# Sheet1.net
KiCad netlist of a schematic drawn in Altium Designer
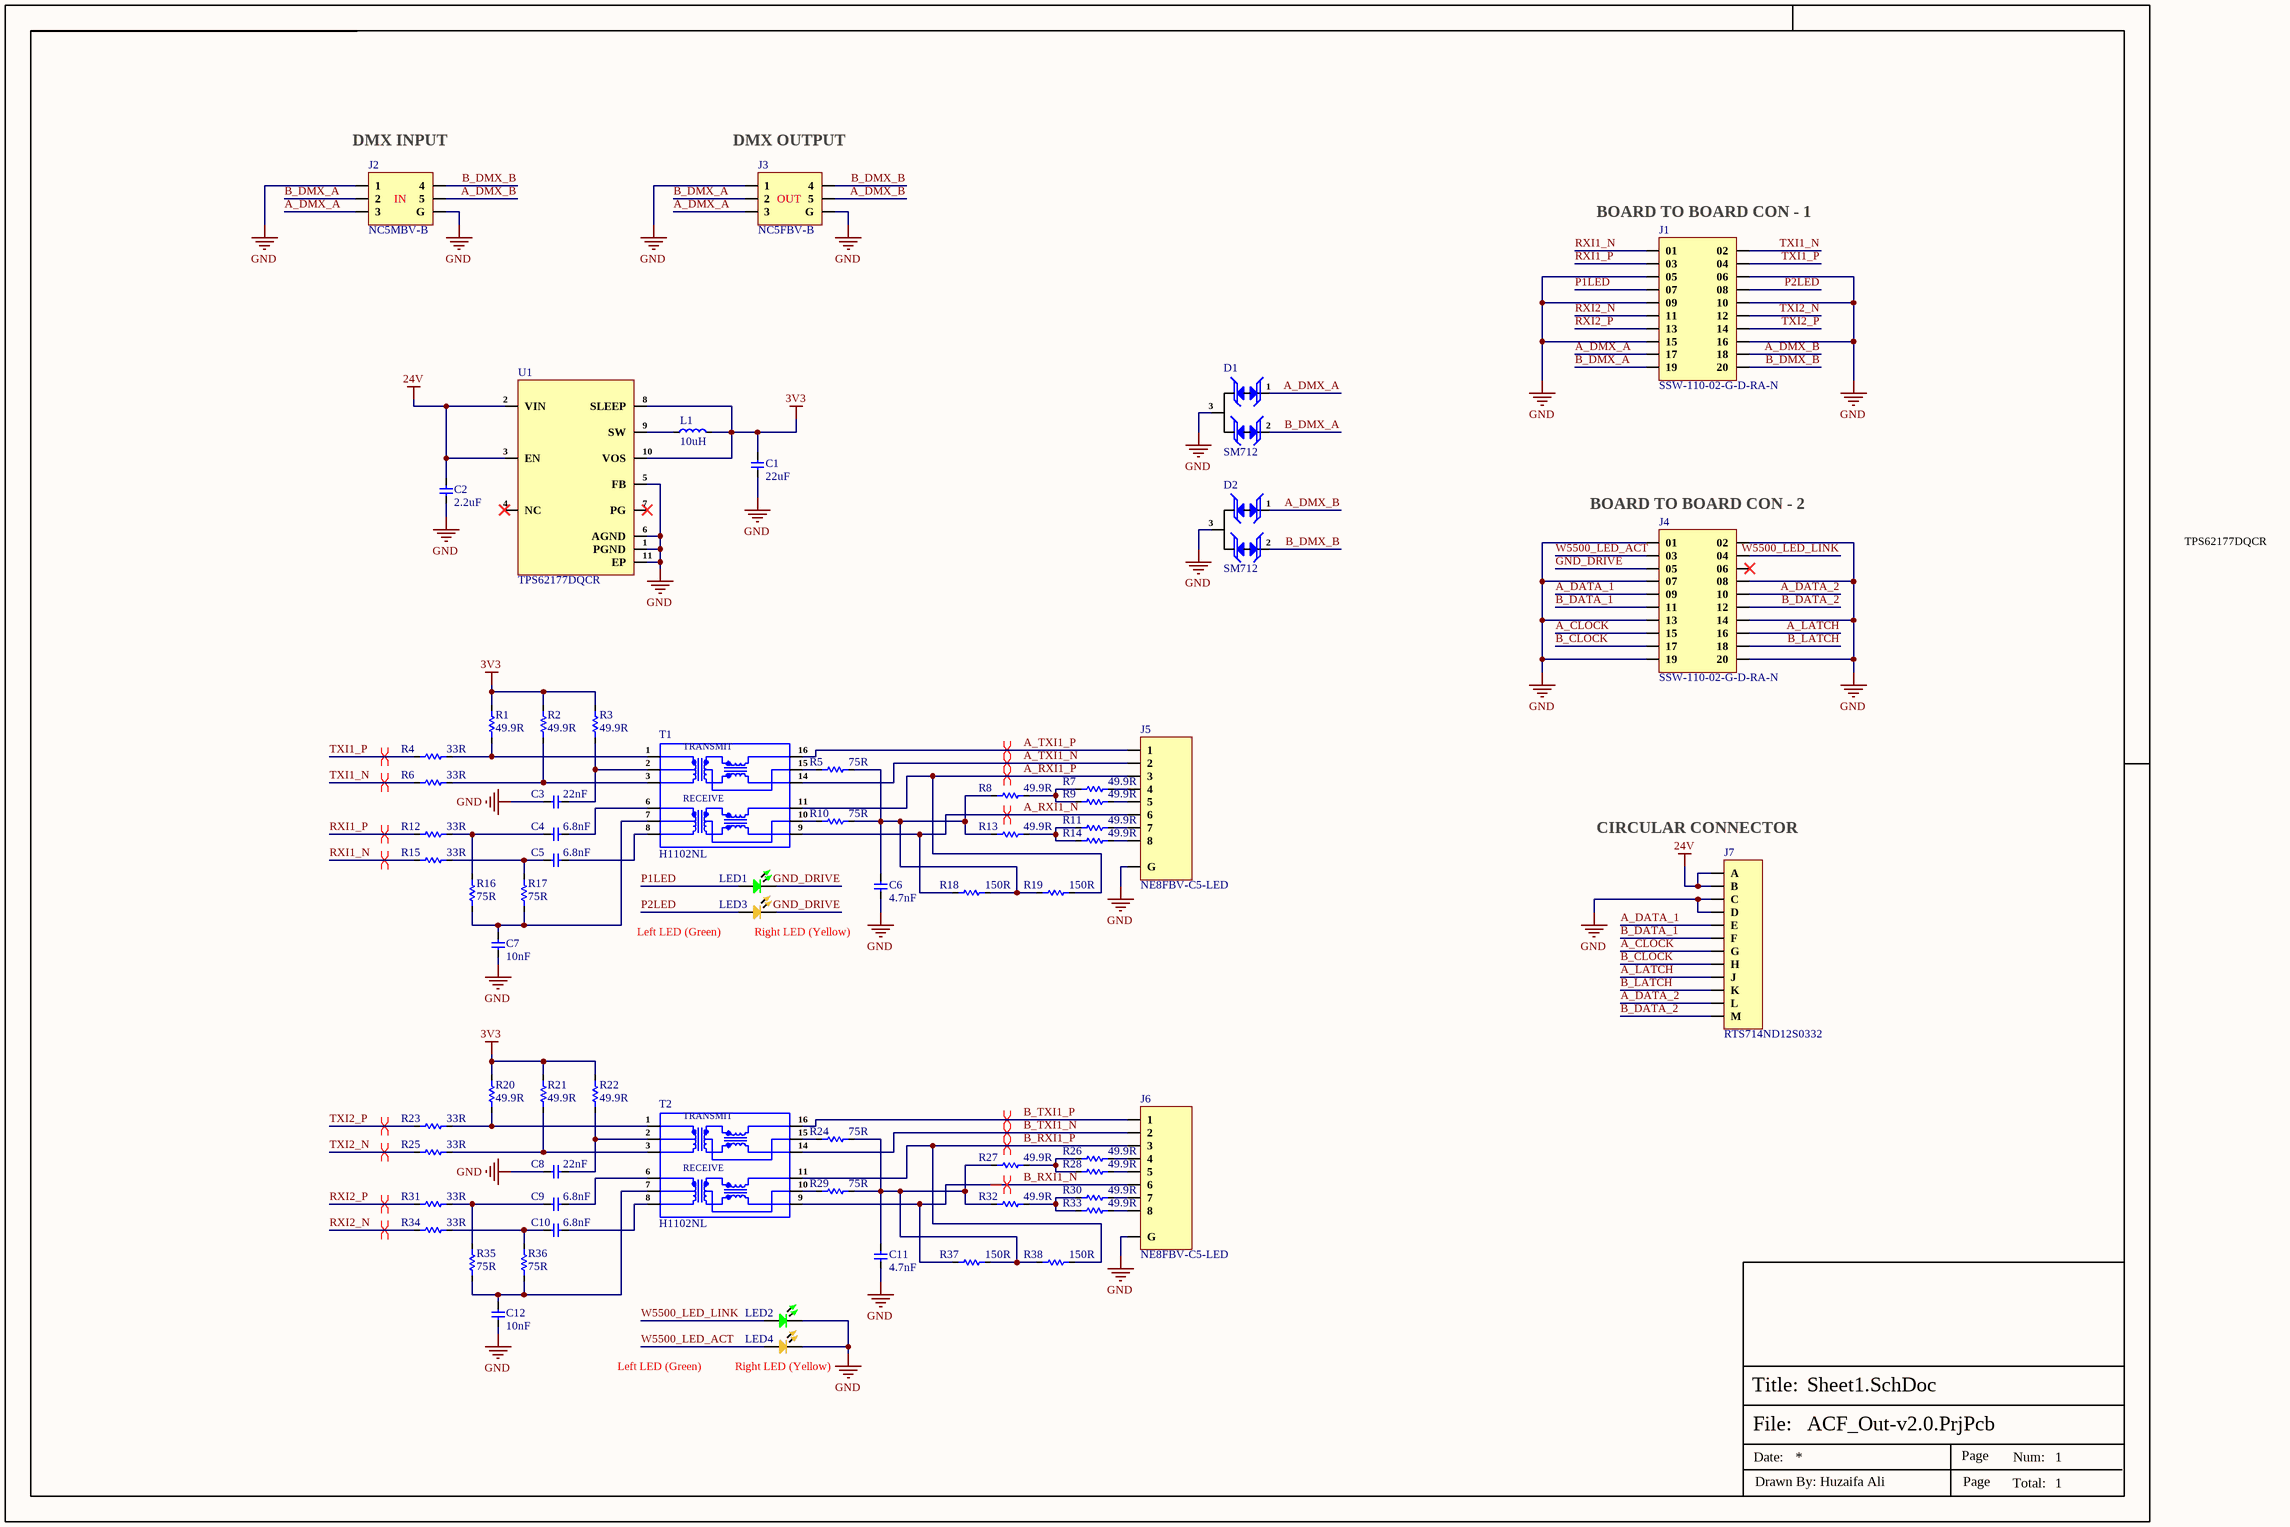
[diagram p0: Sheet1.SchDoc]

(export (version "E")
  (design (tool "Eeschema 10.0.6"))
  (components
    (comp (ref "C1")
      (value "22uF")
      (footprint "Cap-0805")
      (description "CAP CER 22UF 25V X5R 0805")
      (fields
        (field (name "MANUFACTURER") "Yageo")
        (field (name "MANUFACTURER PART NUMBER") "CC0805MKX5R8BB226")
      )
      (libsource (lib "eSpark Libraries") (part "CC0805MKX5R8BB226"))
    )
    (comp (ref "C2")
      (value "2.2uF")
      (footprint "Cap-0805")
      (description "CAP CER 2.2UF 50V X7R 0805")
      (fields (field (name "LCSC PART NUMBER") "C125847") (field (name "MANUFACTURER") "Yageo"))
      (libsource (lib "eSpark Libraries") (part "CC0805KKX7R9BB225"))
    )
    (comp (ref "C3")
      (value "22nF")
      (footprint "Cap-0603")
      (description "CAP CER 0.022UF 50V X7R 0603")
      (fields
        (field (name "MANUFACTURER") "Yageo")
        (field (name "MANUFACTURER PART NUMBER") "CC0603KRX7R9BB223")
      )
      (libsource (lib "eSpark Libraries") (part "CC0603KRX7R9BB223"))
    )
    (comp (ref "C4")
      (value "6.8nF")
      (footprint "Cap-0603")
      (description "50V 6.8nF X7R ±10% 0603")
      (fields (field (name "MANUFACTURER") "FH") (field (name "MANUFACTURER PART NUMBER") "0603B682K500NT"))
      (libsource (lib "eSpark Libraries") (part "0603B682K500NT"))
    )
    (comp (ref "C5")
      (value "6.8nF")
      (footprint "Cap-0603")
      (description "50V 6.8nF X7R ±10% 0603")
      (fields (field (name "MANUFACTURER") "FH") (field (name "MANUFACTURER PART NUMBER") "0603B682K500NT"))
      (libsource (lib "eSpark Libraries") (part "0603B682K500NT"))
    )
    (comp (ref "C6")
      (value "4.7nF")
      (footprint "Cap-1206")
      (description "CAP CER 4700PF 1KV X7R 1206")
      (fields
        (field (name "MANUFACTURER") "Yageo")
        (field (name "MANUFACTURER PART NUMBER") "CC1206KKX7RCBB472")
      )
      (libsource (lib "eSpark Libraries") (part "CC1206KKX7RCBB472"))
    )
    (comp (ref "C7")
      (value "10nF")
      (footprint "Cap-0603")
      (description "CAP CER 10000PF 100V X7R 0603")
      (fields (field (name "LCSC PART NUMBER") "C107059") (field (name "MANUFACTURER") "Yageo"))
      (libsource (lib "eSpark Libraries") (part "CC0603KRX7R0BB103"))
    )
    (comp (ref "C8")
      (value "22nF")
      (footprint "Cap-0603")
      (description "CAP CER 0.022UF 50V X7R 0603")
      (fields
        (field (name "MANUFACTURER") "Yageo")
        (field (name "MANUFACTURER PART NUMBER") "CC0603KRX7R9BB223")
      )
      (libsource (lib "eSpark Libraries") (part "CC0603KRX7R9BB223"))
    )
    (comp (ref "C9")
      (value "6.8nF")
      (footprint "Cap-0603")
      (description "50V 6.8nF X7R ±10% 0603")
      (fields (field (name "MANUFACTURER") "FH") (field (name "MANUFACTURER PART NUMBER") "0603B682K500NT"))
      (libsource (lib "eSpark Libraries") (part "0603B682K500NT"))
    )
    (comp (ref "C10")
      (value "6.8nF")
      (footprint "Cap-0603")
      (description "50V 6.8nF X7R ±10% 0603")
      (fields (field (name "MANUFACTURER") "FH") (field (name "MANUFACTURER PART NUMBER") "0603B682K500NT"))
      (libsource (lib "eSpark Libraries") (part "0603B682K500NT"))
    )
    (comp (ref "C11")
      (value "4.7nF")
      (footprint "Cap-1206")
      (description "CAP CER 4700PF 1KV X7R 1206")
      (fields
        (field (name "MANUFACTURER") "Yageo")
        (field (name "MANUFACTURER PART NUMBER") "CC1206KKX7RCBB472")
      )
      (libsource (lib "eSpark Libraries") (part "CC1206KKX7RCBB472"))
    )
    (comp (ref "C12")
      (value "10nF")
      (footprint "Cap-0603")
      (description "CAP CER 10000PF 100V X7R 0603")
      (fields (field (name "LCSC PART NUMBER") "C107059") (field (name "MANUFACTURER") "Yageo"))
      (libsource (lib "eSpark Libraries") (part "CC0603KRX7R0BB103"))
    )
    (comp (ref "D1")
      (value "SM712")
      (footprint "SOT-23")
      (description "SOT-23 TVS ROHS")
      (fields (field (name "MANUFACTURER") "TECH PUBLIC") (field (name "LCSC PART NUMBER") "C521963"))
      (libsource (lib "eSpark Libraries") (part "SM712"))
    )
    (comp (ref "D2")
      (value "SM712")
      (footprint "SOT-23")
      (description "SOT-23 TVS ROHS")
      (fields (field (name "MANUFACTURER") "TECH PUBLIC") (field (name "LCSC PART NUMBER") "C521963"))
      (libsource (lib "eSpark Libraries") (part "SM712"))
    )
    (comp (ref "J1")
      (value "SSW-110-02-G-D-RA-N")
      (footprint "SSW-110-02-G-D-RA-N")
      (description "CONN RCPT 20POS 0.1 GOLD PCB R/A")
      (fields (field (name "MANUFACTURER") "Samtec"))
      (libsource (lib "eSpark Libraries") (part "SSW-110-02-G-D-RA-N"))
    )
    (comp (ref "J2")
      (value "NC5MBV-B")
      (footprint "NC5MBV-B")
      (description "XLR Connectors 5P M RECEPT B SER PCBV PN 1 GRD SEP BK")
      (fields (field (name "MANUFACTURER") "Neutrik"))
      (libsource (lib "eSpark Libraries") (part "NC5MBV-B"))
    )
    (comp (ref "J3")
      (value "NC5FBV-B")
      (footprint "NC5FBV-B")
      (description "XLR Connectors 5P M RECEPT B SER PCBV PN 1 GRD SEP BK")
      (fields (field (name "MANUFACTURER") "Neutrik"))
      (libsource (lib "eSpark Libraries") (part "NC5FBV-B"))
    )
    (comp (ref "J4")
      (value "SSW-110-02-G-D-RA-N")
      (footprint "SSW-110-02-G-D-RA-N")
      (description "CONN RCPT 20POS 0.1 GOLD PCB R/A")
      (fields (field (name "MANUFACTURER") "Samtec"))
      (libsource (lib "eSpark Libraries") (part "SSW-110-02-G-D-RA-N"))
    )
    (comp (ref "J5")
      (value "NE8FBV-C5-LED")
      (footprint "NE8FBV-C5-LED")
      (description "Modular Connectors / Ethernet Connectors RECP CAT5e B series PCBV, 24mm FP to PCB")
      (fields (field (name "MANUFACTURER") "Neutrik"))
      (libsource (lib "eSpark Libraries") (part "NE8FBV-C5-LED"))
    )
    (comp (ref "J6")
      (value "NE8FBV-C5-LED")
      (footprint "NE8FBV-C5-LED")
      (description "Modular Connectors / Ethernet Connectors RECP CAT5e B series PCBV, 24mm FP to PCB")
      (fields (field (name "MANUFACTURER") "Neutrik"))
      (libsource (lib "eSpark Libraries") (part "NE8FBV-C5-LED"))
    )
    (comp (ref "J7")
      (value "RTS714ND12S0332")
      (footprint "RTS714ND12S0332")
      (description "CONN RCPT FMALE 12P GOLD SOLDER")
      (fields (field (name "MANUFACTURER") "Amphenol Sine Systems"))
      (libsource (lib "eSpark Libraries") (part "RTS714ND12S0332"))
    )
    (comp (ref "L1")
      (value "10uH")
      (footprint "IND-1008 (2520 Metric)")
      (description "FIXED IND 10UH 1A 540 MOHM SMD")
      (fields
        (field (name "MANUFACTURER") "TDK")
        (field (name "MANUFACTURER PART NUMBER") "VLS252012HBX-100M-1")
      )
      (libsource (lib "eSpark Libraries") (part "VLS252012HBX-100M-1"))
    )
    (comp (ref "LED1")
      (value "Emerald")
      (footprint "TH LED 3mm_")
      (description "515nm~525nm -30℃~+85℃ Emerald 30° 200mW Plugin,D=3mm Light Emitting Diodes (LED) ROHS")
      (fields
        (field (name "MANUFACTURER") "Foshan NationStar Optoelectronics")
        (field (name "MANUFACTURER PART NUMBER") "NFD3401UGD")
      )
      (libsource (lib "eSpark Libraries") (part "NFD3401UGD"))
    )
    (comp (ref "LED2")
      (value "Emerald")
      (footprint "TH LED 3mm_")
      (description "515nm~525nm -30℃~+85℃ Emerald 30° 200mW Plugin,D=3mm Light Emitting Diodes (LED) ROHS")
      (fields
        (field (name "MANUFACTURER") "Foshan NationStar Optoelectronics")
        (field (name "MANUFACTURER PART NUMBER") "NFD3401UGD")
      )
      (libsource (lib "eSpark Libraries") (part "NFD3401UGD"))
    )
    (comp (ref "LED3")
      (value "Yellow")
      (footprint "TH LED Yellow 3MM")
      (description "585nm~595nm -30℃~+85℃ Yellow 30° 200mW Plugin,D=3mm Light Emitting Diodes (LED) ROHS")
      (fields
        (field (name "MANUFACTURER") "Foshan NationStar Optoelectronics")
        (field (name "MANUFACTURER PART NUMBER") "NFD3401UYD")
      )
      (libsource (lib "eSpark Libraries") (part "NFD3401UYD"))
    )
    (comp (ref "LED4")
      (value "Yellow")
      (footprint "TH LED Yellow 3MM")
      (description "585nm~595nm -30℃~+85℃ Yellow 30° 200mW Plugin,D=3mm Light Emitting Diodes (LED) ROHS")
      (fields
        (field (name "MANUFACTURER") "Foshan NationStar Optoelectronics")
        (field (name "MANUFACTURER PART NUMBER") "NFD3401UYD")
      )
      (libsource (lib "eSpark Libraries") (part "NFD3401UYD"))
    )
    (comp (ref "R1")
      (value "49.9R")
      (footprint "Res-0603")
      (description "RES 49.9 OHM 1% 1/10W 0603")
      (fields
        (field (name "MANUFACTURER") "Yageo")
        (field (name "MANUFACTURER PART NUMBER") "RC0603FR-0749R9L")
      )
      (libsource (lib "eSpark Libraries") (part "RC0603FR-0749R9L"))
    )
    (comp (ref "R2")
      (value "49.9R")
      (footprint "Res-0603")
      (description "RES 49.9 OHM 1% 1/10W 0603")
      (fields
        (field (name "MANUFACTURER") "Yageo")
        (field (name "MANUFACTURER PART NUMBER") "RC0603FR-0749R9L")
      )
      (libsource (lib "eSpark Libraries") (part "RC0603FR-0749R9L"))
    )
    (comp (ref "R3")
      (value "49.9R")
      (footprint "Res-0603")
      (description "RES 49.9 OHM 1% 1/10W 0603")
      (fields
        (field (name "MANUFACTURER") "Yageo")
        (field (name "MANUFACTURER PART NUMBER") "RC0603FR-0749R9L")
      )
      (libsource (lib "eSpark Libraries") (part "RC0603FR-0749R9L"))
    )
    (comp (ref "R4")
      (value "33R")
      (footprint "Res-0603")
      (description "RES SMD 0603 33 Ohm 1% 1/10W")
      (fields
        (field (name "MANUFACTURER") "Yageo")
        (field (name "MANUFACTURER PART NUMBER") "RC0603FR-0733RL")
      )
      (libsource (lib "eSpark Libraries") (part "RC0603FR-0733RL"))
    )
    (comp (ref "R5")
      (value "75R")
      (footprint "Res-0603")
      (description "RES 75 OHM 1% 1/10W 0603")
      (fields
        (field (name "MANUFACTURER") "Yageo")
        (field (name "MANUFACTURER PART NUMBER") "RC0603FR-0775RL")
      )
      (libsource (lib "eSpark Libraries") (part "RC0603FR-0775RL"))
    )
    (comp (ref "R6")
      (value "33R")
      (footprint "Res-0603")
      (description "RES SMD 0603 33 Ohm 1% 1/10W")
      (fields
        (field (name "MANUFACTURER") "Yageo")
        (field (name "MANUFACTURER PART NUMBER") "RC0603FR-0733RL")
      )
      (libsource (lib "eSpark Libraries") (part "RC0603FR-0733RL"))
    )
    (comp (ref "R7")
      (value "49.9R")
      (footprint "Res-0603")
      (description "RES 49.9 OHM 1% 1/10W 0603")
      (fields
        (field (name "MANUFACTURER") "Yageo")
        (field (name "MANUFACTURER PART NUMBER") "RC0603FR-0749R9L")
      )
      (libsource (lib "eSpark Libraries") (part "RC0603FR-0749R9L"))
    )
    (comp (ref "R8")
      (value "49.9R")
      (footprint "Res-0603")
      (description "RES 49.9 OHM 1% 1/10W 0603")
      (fields
        (field (name "MANUFACTURER") "Yageo")
        (field (name "MANUFACTURER PART NUMBER") "RC0603FR-0749R9L")
      )
      (libsource (lib "eSpark Libraries") (part "RC0603FR-0749R9L"))
    )
    (comp (ref "R9")
      (value "49.9R")
      (footprint "Res-0603")
      (description "RES 49.9 OHM 1% 1/10W 0603")
      (fields
        (field (name "MANUFACTURER") "Yageo")
        (field (name "MANUFACTURER PART NUMBER") "RC0603FR-0749R9L")
      )
      (libsource (lib "eSpark Libraries") (part "RC0603FR-0749R9L"))
    )
    (comp (ref "R10")
      (value "75R")
      (footprint "Res-0603")
      (description "RES 75 OHM 1% 1/10W 0603")
      (fields
        (field (name "MANUFACTURER") "Yageo")
        (field (name "MANUFACTURER PART NUMBER") "RC0603FR-0775RL")
      )
      (libsource (lib "eSpark Libraries") (part "RC0603FR-0775RL"))
    )
    (comp (ref "R11")
      (value "49.9R")
      (footprint "Res-0603")
      (description "RES 49.9 OHM 1% 1/10W 0603")
      (fields
        (field (name "MANUFACTURER") "Yageo")
        (field (name "MANUFACTURER PART NUMBER") "RC0603FR-0749R9L")
      )
      (libsource (lib "eSpark Libraries") (part "RC0603FR-0749R9L"))
    )
    (comp (ref "R12")
      (value "33R")
      (footprint "Res-0603")
      (description "RES SMD 0603 33 Ohm 1% 1/10W")
      (fields
        (field (name "MANUFACTURER") "Yageo")
        (field (name "MANUFACTURER PART NUMBER") "RC0603FR-0733RL")
      )
      (libsource (lib "eSpark Libraries") (part "RC0603FR-0733RL"))
    )
    (comp (ref "R13")
      (value "49.9R")
      (footprint "Res-0603")
      (description "RES 49.9 OHM 1% 1/10W 0603")
      (fields
        (field (name "MANUFACTURER") "Yageo")
        (field (name "MANUFACTURER PART NUMBER") "RC0603FR-0749R9L")
      )
      (libsource (lib "eSpark Libraries") (part "RC0603FR-0749R9L"))
    )
    (comp (ref "R14")
      (value "49.9R")
      (footprint "Res-0603")
      (description "RES 49.9 OHM 1% 1/10W 0603")
      (fields
        (field (name "MANUFACTURER") "Yageo")
        (field (name "MANUFACTURER PART NUMBER") "RC0603FR-0749R9L")
      )
      (libsource (lib "eSpark Libraries") (part "RC0603FR-0749R9L"))
    )
    (comp (ref "R15")
      (value "33R")
      (footprint "Res-0603")
      (description "RES SMD 0603 33 Ohm 1% 1/10W")
      (fields
        (field (name "MANUFACTURER") "Yageo")
        (field (name "MANUFACTURER PART NUMBER") "RC0603FR-0733RL")
      )
      (libsource (lib "eSpark Libraries") (part "RC0603FR-0733RL"))
    )
    (comp (ref "R16")
      (value "75R")
      (footprint "Res-0603")
      (description "RES 75 OHM 1% 1/10W 0603")
      (fields
        (field (name "MANUFACTURER") "Yageo")
        (field (name "MANUFACTURER PART NUMBER") "RC0603FR-0775RL")
      )
      (libsource (lib "eSpark Libraries") (part "RC0603FR-0775RL"))
    )
    (comp (ref "R17")
      (value "75R")
      (footprint "Res-0603")
      (description "RES 75 OHM 1% 1/10W 0603")
      (fields
        (field (name "MANUFACTURER") "Yageo")
        (field (name "MANUFACTURER PART NUMBER") "RC0603FR-0775RL")
      )
      (libsource (lib "eSpark Libraries") (part "RC0603FR-0775RL"))
    )
    (comp (ref "R18")
      (value "150R")
      (footprint "Res-0603")
      (description "RES SMD 150OHM 1/10W 0603")
      (fields
        (field (name "MANUFACTURER") "Yageo")
        (field (name "MANUFACTURER PART NUMBER") "RC0603FR-07150RL")
      )
      (libsource (lib "eSpark Libraries") (part "RC0603FR-07150RL"))
    )
    (comp (ref "R19")
      (value "150R")
      (footprint "Res-0603")
      (description "RES SMD 150OHM 1/10W 0603")
      (fields
        (field (name "MANUFACTURER") "Yageo")
        (field (name "MANUFACTURER PART NUMBER") "RC0603FR-07150RL")
      )
      (libsource (lib "eSpark Libraries") (part "RC0603FR-07150RL"))
    )
    (comp (ref "R20")
      (value "49.9R")
      (footprint "Res-0603")
      (description "RES 49.9 OHM 1% 1/10W 0603")
      (fields
        (field (name "MANUFACTURER") "Yageo")
        (field (name "MANUFACTURER PART NUMBER") "RC0603FR-0749R9L")
      )
      (libsource (lib "eSpark Libraries") (part "RC0603FR-0749R9L"))
    )
    (comp (ref "R21")
      (value "49.9R")
      (footprint "Res-0603")
      (description "RES 49.9 OHM 1% 1/10W 0603")
      (fields
        (field (name "MANUFACTURER") "Yageo")
        (field (name "MANUFACTURER PART NUMBER") "RC0603FR-0749R9L")
      )
      (libsource (lib "eSpark Libraries") (part "RC0603FR-0749R9L"))
    )
    (comp (ref "R22")
      (value "49.9R")
      (footprint "Res-0603")
      (description "RES 49.9 OHM 1% 1/10W 0603")
      (fields
        (field (name "MANUFACTURER") "Yageo")
        (field (name "MANUFACTURER PART NUMBER") "RC0603FR-0749R9L")
      )
      (libsource (lib "eSpark Libraries") (part "RC0603FR-0749R9L"))
    )
    (comp (ref "R23")
      (value "33R")
      (footprint "Res-0603")
      (description "RES SMD 0603 33 Ohm 1% 1/10W")
      (fields
        (field (name "MANUFACTURER") "Yageo")
        (field (name "MANUFACTURER PART NUMBER") "RC0603FR-0733RL")
      )
      (libsource (lib "eSpark Libraries") (part "RC0603FR-0733RL"))
    )
    (comp (ref "R24")
      (value "75R")
      (footprint "Res-0603")
      (description "RES 75 OHM 1% 1/10W 0603")
      (fields
        (field (name "MANUFACTURER") "Yageo")
        (field (name "MANUFACTURER PART NUMBER") "RC0603FR-0775RL")
      )
      (libsource (lib "eSpark Libraries") (part "RC0603FR-0775RL"))
    )
    (comp (ref "R25")
      (value "33R")
      (footprint "Res-0603")
      (description "RES SMD 0603 33 Ohm 1% 1/10W")
      (fields
        (field (name "MANUFACTURER") "Yageo")
        (field (name "MANUFACTURER PART NUMBER") "RC0603FR-0733RL")
      )
      (libsource (lib "eSpark Libraries") (part "RC0603FR-0733RL"))
    )
    (comp (ref "R26")
      (value "49.9R")
      (footprint "Res-0603")
      (description "RES 49.9 OHM 1% 1/10W 0603")
      (fields
        (field (name "MANUFACTURER") "Yageo")
        (field (name "MANUFACTURER PART NUMBER") "RC0603FR-0749R9L")
      )
      (libsource (lib "eSpark Libraries") (part "RC0603FR-0749R9L"))
    )
    (comp (ref "R27")
      (value "49.9R")
      (footprint "Res-0603")
      (description "RES 49.9 OHM 1% 1/10W 0603")
      (fields
        (field (name "MANUFACTURER") "Yageo")
        (field (name "MANUFACTURER PART NUMBER") "RC0603FR-0749R9L")
      )
      (libsource (lib "eSpark Libraries") (part "RC0603FR-0749R9L"))
    )
    (comp (ref "R28")
      (value "49.9R")
      (footprint "Res-0603")
      (description "RES 49.9 OHM 1% 1/10W 0603")
      (fields
        (field (name "MANUFACTURER") "Yageo")
        (field (name "MANUFACTURER PART NUMBER") "RC0603FR-0749R9L")
      )
      (libsource (lib "eSpark Libraries") (part "RC0603FR-0749R9L"))
    )
    (comp (ref "R29")
      (value "75R")
      (footprint "Res-0603")
      (description "RES 75 OHM 1% 1/10W 0603")
      (fields
        (field (name "MANUFACTURER") "Yageo")
        (field (name "MANUFACTURER PART NUMBER") "RC0603FR-0775RL")
      )
      (libsource (lib "eSpark Libraries") (part "RC0603FR-0775RL"))
    )
    (comp (ref "R30")
      (value "49.9R")
      (footprint "Res-0603")
      (description "RES 49.9 OHM 1% 1/10W 0603")
      (fields
        (field (name "MANUFACTURER") "Yageo")
        (field (name "MANUFACTURER PART NUMBER") "RC0603FR-0749R9L")
      )
      (libsource (lib "eSpark Libraries") (part "RC0603FR-0749R9L"))
    )
    (comp (ref "R31")
      (value "33R")
      (footprint "Res-0603")
      (description "RES SMD 0603 33 Ohm 1% 1/10W")
      (fields
        (field (name "MANUFACTURER") "Yageo")
        (field (name "MANUFACTURER PART NUMBER") "RC0603FR-0733RL")
      )
      (libsource (lib "eSpark Libraries") (part "RC0603FR-0733RL"))
    )
    (comp (ref "R32")
      (value "49.9R")
      (footprint "Res-0603")
      (description "RES 49.9 OHM 1% 1/10W 0603")
      (fields
        (field (name "MANUFACTURER") "Yageo")
        (field (name "MANUFACTURER PART NUMBER") "RC0603FR-0749R9L")
      )
      (libsource (lib "eSpark Libraries") (part "RC0603FR-0749R9L"))
    )
    (comp (ref "R33")
      (value "49.9R")
      (footprint "Res-0603")
      (description "RES 49.9 OHM 1% 1/10W 0603")
      (fields
        (field (name "MANUFACTURER") "Yageo")
        (field (name "MANUFACTURER PART NUMBER") "RC0603FR-0749R9L")
      )
      (libsource (lib "eSpark Libraries") (part "RC0603FR-0749R9L"))
    )
    (comp (ref "R34")
      (value "33R")
      (footprint "Res-0603")
      (description "RES SMD 0603 33 Ohm 1% 1/10W")
      (fields
        (field (name "MANUFACTURER") "Yageo")
        (field (name "MANUFACTURER PART NUMBER") "RC0603FR-0733RL")
      )
      (libsource (lib "eSpark Libraries") (part "RC0603FR-0733RL"))
    )
    (comp (ref "R35")
      (value "75R")
      (footprint "Res-0603")
      (description "RES 75 OHM 1% 1/10W 0603")
      (fields
        (field (name "MANUFACTURER") "Yageo")
        (field (name "MANUFACTURER PART NUMBER") "RC0603FR-0775RL")
      )
      (libsource (lib "eSpark Libraries") (part "RC0603FR-0775RL"))
    )
    (comp (ref "R36")
      (value "75R")
      (footprint "Res-0603")
      (description "RES 75 OHM 1% 1/10W 0603")
      (fields
        (field (name "MANUFACTURER") "Yageo")
        (field (name "MANUFACTURER PART NUMBER") "RC0603FR-0775RL")
      )
      (libsource (lib "eSpark Libraries") (part "RC0603FR-0775RL"))
    )
    (comp (ref "R37")
      (value "150R")
      (footprint "Res-0603")
      (description "RES SMD 150OHM 1/10W 0603")
      (fields
        (field (name "MANUFACTURER") "Yageo")
        (field (name "MANUFACTURER PART NUMBER") "RC0603FR-07150RL")
      )
      (libsource (lib "eSpark Libraries") (part "RC0603FR-07150RL"))
    )
    (comp (ref "R38")
      (value "150R")
      (footprint "Res-0603")
      (description "RES SMD 150OHM 1/10W 0603")
      (fields
        (field (name "MANUFACTURER") "Yageo")
        (field (name "MANUFACTURER PART NUMBER") "RC0603FR-07150RL")
      )
      (libsource (lib "eSpark Libraries") (part "RC0603FR-07150RL"))
    )
    (comp (ref "T1")
      (value "H1102NL")
      (footprint "H1102NLT")
      (description "XFRMR MAGNETIC 1PORT 1:1 10/100")
      (fields (field (name "MANUFACTURER") "Pulse") (field (name "LCSC PART NUMBER") "C18584"))
      (libsource (lib "eSpark Libraries") (part "H1102NL"))
    )
    (comp (ref "T2")
      (value "H1102NL")
      (footprint "H1102NLT")
      (description "XFRMR MAGNETIC 1PORT 1:1 10/100")
      (fields (field (name "MANUFACTURER") "Pulse") (field (name "LCSC PART NUMBER") "C18584"))
      (libsource (lib "eSpark Libraries") (part "H1102NL"))
    )
    (comp (ref "U1")
      (value "TPS62177DQCR")
      (footprint "10-WSON (3x2)")
      (description "IC REG BUCK 3.3V 500MA 10WSON")
      (fields (field (name "LCSC PART NUMBER") "C91241") (field (name "MANUFACTURER") "Texas Instruments"))
      (libsource (lib "eSpark Libraries") (part "TPS62177DQCR"))
    )
  )
  (nets
    (net (code "1") (name "/A_CLOCK") (class "Default")
      (node (ref "J4") (pin "15") (pinfunction "15_15") (pintype "passive"))
      (node (ref "J7") (pin "G") (pinfunction "G_G") (pintype "passive"))
    )
    (net (code "2") (name "/A_DATA_1") (class "Default")
      (node (ref "J4") (pin "09") (pinfunction "09_09") (pintype "passive"))
      (node (ref "J7") (pin "E") (pinfunction "E_E") (pintype "passive"))
    )
    (net (code "3") (name "/A_DATA_2") (class "Default")
      (node (ref "J4") (pin "10") (pinfunction "10_10") (pintype "passive"))
      (node (ref "J7") (pin "L") (pinfunction "L_L") (pintype "passive"))
    )
    (net (code "4") (name "/A_DMX_A") (class "Default")
      (node (ref "D1") (pin "1") (pinfunction "I/O1_1") (pintype "passive"))
      (node (ref "J1") (pin "17") (pinfunction "17_17") (pintype "passive"))
      (node (ref "J2") (pin "3") (pinfunction "3_3") (pintype "passive"))
      (node (ref "J3") (pin "3") (pinfunction "3_3") (pintype "passive"))
    )
    (net (code "5") (name "/A_DMX_B") (class "Default")
      (node (ref "D2") (pin "1") (pinfunction "I/O1_1") (pintype "passive"))
      (node (ref "J1") (pin "18") (pinfunction "18_18") (pintype "passive"))
      (node (ref "J2") (pin "5") (pinfunction "5_5") (pintype "passive"))
      (node (ref "J3") (pin "5") (pinfunction "5_5") (pintype "passive"))
    )
    (net (code "6") (name "/A_LATCH") (class "Default")
      (node (ref "J4") (pin "16") (pinfunction "16_16") (pintype "passive"))
      (node (ref "J7") (pin "J") (pinfunction "J_J") (pintype "passive"))
    )
    (net (code "7") (name "/A_RXI1_N") (class "Default")
      (node (ref "J5") (pin "6") (pinfunction "6_6") (pintype "passive"))
      (node (ref "R18") (pin "2") (pinfunction "2_2") (pintype "passive"))
      (node (ref "T1") (pin "9") (pinfunction "9_9") (pintype "passive"))
    )
    (net (code "8") (name "/A_RXI1_P") (class "Default")
      (node (ref "J5") (pin "3") (pinfunction "3_3") (pintype "passive"))
      (node (ref "R19") (pin "1") (pinfunction "1_1") (pintype "passive"))
      (node (ref "T1") (pin "11") (pinfunction "11_11") (pintype "passive"))
    )
    (net (code "9") (name "/A_TXI1_N") (class "Default")
      (node (ref "J5") (pin "2") (pinfunction "2_2") (pintype "passive"))
      (node (ref "T1") (pin "14") (pinfunction "14_14") (pintype "passive"))
    )
    (net (code "10") (name "/A_TXI1_P") (class "Default")
      (node (ref "J5") (pin "1") (pinfunction "1_1") (pintype "passive"))
      (node (ref "T1") (pin "16") (pinfunction "16_16") (pintype "passive"))
    )
    (net (code "11") (name "/B_CLOCK") (class "Default")
      (node (ref "J4") (pin "17") (pinfunction "17_17") (pintype "passive"))
      (node (ref "J7") (pin "H") (pinfunction "H_H") (pintype "passive"))
    )
    (net (code "12") (name "/B_DATA_1") (class "Default")
      (node (ref "J4") (pin "11") (pinfunction "11_11") (pintype "passive"))
      (node (ref "J7") (pin "F") (pinfunction "F_F") (pintype "passive"))
    )
    (net (code "13") (name "/B_DATA_2") (class "Default")
      (node (ref "J4") (pin "12") (pinfunction "12_12") (pintype "passive"))
      (node (ref "J7") (pin "M") (pinfunction "M_M") (pintype "passive"))
    )
    (net (code "14") (name "/B_DMX_A") (class "Default")
      (node (ref "D1") (pin "2") (pinfunction "I/O2_2") (pintype "passive"))
      (node (ref "J1") (pin "19") (pinfunction "19_19") (pintype "passive"))
      (node (ref "J2") (pin "2") (pinfunction "2_2") (pintype "passive"))
      (node (ref "J3") (pin "2") (pinfunction "2_2") (pintype "passive"))
    )
    (net (code "15") (name "/B_DMX_B") (class "Default")
      (node (ref "D2") (pin "2") (pinfunction "I/O2_2") (pintype "passive"))
      (node (ref "J1") (pin "20") (pinfunction "20_20") (pintype "passive"))
      (node (ref "J2") (pin "4") (pinfunction "4_4") (pintype "passive"))
      (node (ref "J3") (pin "4") (pinfunction "4_4") (pintype "passive"))
    )
    (net (code "16") (name "/B_LATCH") (class "Default")
      (node (ref "J4") (pin "18") (pinfunction "18_18") (pintype "passive"))
      (node (ref "J7") (pin "K") (pinfunction "K_K") (pintype "passive"))
    )
    (net (code "17") (name "/B_RXI1_N") (class "Default")
      (node (ref "J6") (pin "6") (pinfunction "6_6") (pintype "passive"))
      (node (ref "R37") (pin "2") (pinfunction "2_2") (pintype "passive"))
      (node (ref "T2") (pin "9") (pinfunction "9_9") (pintype "passive"))
    )
    (net (code "18") (name "/B_RXI1_P") (class "Default")
      (node (ref "J6") (pin "3") (pinfunction "3_3") (pintype "passive"))
      (node (ref "R38") (pin "1") (pinfunction "1_1") (pintype "passive"))
      (node (ref "T2") (pin "11") (pinfunction "11_11") (pintype "passive"))
    )
    (net (code "19") (name "/B_TXI1_N") (class "Default")
      (node (ref "J6") (pin "2") (pinfunction "2_2") (pintype "passive"))
      (node (ref "T2") (pin "14") (pinfunction "14_14") (pintype "passive"))
    )
    (net (code "20") (name "/B_TXI1_P") (class "Default")
      (node (ref "J6") (pin "1") (pinfunction "1_1") (pintype "passive"))
      (node (ref "T2") (pin "16") (pinfunction "16_16") (pintype "passive"))
    )
    (net (code "21") (name "/GND_DRIVE") (class "Default")
      (node (ref "J4") (pin "05") (pinfunction "05_05") (pintype "passive"))
      (node (ref "LED1") (pin "1") (pinfunction "-_1") (pintype "passive"))
      (node (ref "LED3") (pin "2") (pinfunction "2_2") (pintype "passive"))
    )
    (net (code "22") (name "/P1LED") (class "Default")
      (node (ref "J1") (pin "07") (pinfunction "07_07") (pintype "passive"))
      (node (ref "LED1") (pin "2") (pinfunction "+_2") (pintype "passive"))
    )
    (net (code "23") (name "/P2LED") (class "Default")
      (node (ref "J1") (pin "08") (pinfunction "08_08") (pintype "passive"))
      (node (ref "LED3") (pin "1") (pinfunction "1_1") (pintype "passive"))
    )
    (net (code "24") (name "/RXI1_N") (class "Default")
      (node (ref "J1") (pin "01") (pinfunction "01_01") (pintype "passive"))
      (node (ref "R15") (pin "1") (pinfunction "1_1") (pintype "passive"))
    )
    (net (code "25") (name "/RXI1_P") (class "Default")
      (node (ref "J1") (pin "03") (pinfunction "03_03") (pintype "passive"))
      (node (ref "R12") (pin "1") (pinfunction "1_1") (pintype "passive"))
    )
    (net (code "26") (name "/RXI2_N") (class "Default")
      (node (ref "J1") (pin "11") (pinfunction "11_11") (pintype "passive"))
      (node (ref "R34") (pin "1") (pinfunction "1_1") (pintype "passive"))
    )
    (net (code "27") (name "/RXI2_P") (class "Default")
      (node (ref "J1") (pin "13") (pinfunction "13_13") (pintype "passive"))
      (node (ref "R31") (pin "1") (pinfunction "1_1") (pintype "passive"))
    )
    (net (code "28") (name "/TXI1_N") (class "Default")
      (node (ref "J1") (pin "02") (pinfunction "02_02") (pintype "passive"))
      (node (ref "R6") (pin "1") (pinfunction "1_1") (pintype "passive"))
    )
    (net (code "29") (name "/TXI1_P") (class "Default")
      (node (ref "J1") (pin "04") (pinfunction "04_04") (pintype "passive"))
      (node (ref "R4") (pin "1") (pinfunction "1_1") (pintype "passive"))
    )
    (net (code "30") (name "/TXI2_N") (class "Default")
      (node (ref "J1") (pin "12") (pinfunction "12_12") (pintype "passive"))
      (node (ref "R25") (pin "1") (pinfunction "1_1") (pintype "passive"))
    )
    (net (code "31") (name "/TXI2_P") (class "Default")
      (node (ref "J1") (pin "14") (pinfunction "14_14") (pintype "passive"))
      (node (ref "R23") (pin "1") (pinfunction "1_1") (pintype "passive"))
    )
    (net (code "32") (name "/W5500_LED_ACT") (class "Default")
      (node (ref "J4") (pin "03") (pinfunction "03_03") (pintype "passive"))
      (node (ref "LED4") (pin "1") (pinfunction "1_1") (pintype "passive"))
    )
    (net (code "33") (name "/W5500_LED_LINK") (class "Default")
      (node (ref "J4") (pin "04") (pinfunction "04_04") (pintype "passive"))
      (node (ref "LED2") (pin "2") (pinfunction "+_2") (pintype "passive"))
    )
    (net (code "34") (name "3V3") (class "Default")
      (node (ref "C1") (pin "2") (pinfunction "2_2") (pintype "passive"))
      (node (ref "L1") (pin "2") (pinfunction "2_2") (pintype "passive"))
      (node (ref "R1") (pin "1") (pinfunction "1_1") (pintype "passive"))
      (node (ref "R2") (pin "1") (pinfunction "1_1") (pintype "passive"))
      (node (ref "R20") (pin "1") (pinfunction "1_1") (pintype "passive"))
      (node (ref "R21") (pin "1") (pinfunction "1_1") (pintype "passive"))
      (node (ref "R22") (pin "1") (pinfunction "1_1") (pintype "passive"))
      (node (ref "R3") (pin "1") (pinfunction "1_1") (pintype "passive"))
      (node (ref "U1") (pin "10") (pinfunction "VOS_10") (pintype "passive"))
      (node (ref "U1") (pin "8") (pinfunction "SLEEP_8") (pintype "passive"))
    )
    (net (code "35") (name "24V") (class "Default")
      (node (ref "C2") (pin "2") (pinfunction "2_2") (pintype "passive"))
      (node (ref "J7") (pin "A") (pinfunction "A_A") (pintype "passive"))
      (node (ref "J7") (pin "B") (pinfunction "B_B") (pintype "passive"))
      (node (ref "U1") (pin "2") (pinfunction "VIN_2") (pintype "passive"))
      (node (ref "U1") (pin "3") (pinfunction "EN_3") (pintype "passive"))
    )
    (net (code "36") (name "GND") (class "Default")
      (node (ref "C1") (pin "1") (pinfunction "1_1") (pintype "passive"))
      (node (ref "C11") (pin "1") (pinfunction "1_1") (pintype "passive"))
      (node (ref "C12") (pin "1") (pinfunction "1_1") (pintype "passive"))
      (node (ref "C2") (pin "1") (pinfunction "1_1") (pintype "passive"))
      (node (ref "C3") (pin "1") (pinfunction "1_1") (pintype "passive"))
      (node (ref "C6") (pin "1") (pinfunction "1_1") (pintype "passive"))
      (node (ref "C7") (pin "1") (pinfunction "1_1") (pintype "passive"))
      (node (ref "C8") (pin "1") (pinfunction "1_1") (pintype "passive"))
      (node (ref "D1") (pin "3") (pinfunction "GND_3") (pintype "passive"))
      (node (ref "D2") (pin "3") (pinfunction "GND_3") (pintype "passive"))
      (node (ref "J1") (pin "05") (pinfunction "05_05") (pintype "passive"))
      (node (ref "J1") (pin "06") (pinfunction "06_06") (pintype "passive"))
      (node (ref "J1") (pin "09") (pinfunction "09_09") (pintype "passive"))
      (node (ref "J1") (pin "10") (pinfunction "10_10") (pintype "passive"))
      (node (ref "J1") (pin "15") (pinfunction "15_15") (pintype "passive"))
      (node (ref "J1") (pin "16") (pinfunction "16_16") (pintype "passive"))
      (node (ref "J2") (pin "1") (pinfunction "1_1") (pintype "passive"))
      (node (ref "J2") (pin "G") (pinfunction "G_G") (pintype "passive"))
      (node (ref "J3") (pin "1") (pinfunction "1_1") (pintype "passive"))
      (node (ref "J3") (pin "G") (pinfunction "G_G") (pintype "passive"))
      (node (ref "J4") (pin "01") (pinfunction "01_01") (pintype "passive"))
      (node (ref "J4") (pin "02") (pinfunction "02_02") (pintype "passive"))
      (node (ref "J4") (pin "07") (pinfunction "07_07") (pintype "passive"))
      (node (ref "J4") (pin "08") (pinfunction "08_08") (pintype "passive"))
      (node (ref "J4") (pin "13") (pinfunction "13_13") (pintype "passive"))
      (node (ref "J4") (pin "14") (pinfunction "14_14") (pintype "passive"))
      (node (ref "J4") (pin "19") (pinfunction "19_19") (pintype "passive"))
      (node (ref "J4") (pin "20") (pinfunction "20_20") (pintype "passive"))
      (node (ref "J5") (pin "G") (pinfunction "G_G") (pintype "power_in"))
      (node (ref "J6") (pin "G") (pinfunction "G_G") (pintype "power_in"))
      (node (ref "J7") (pin "C") (pinfunction "C_C") (pintype "passive"))
      (node (ref "J7") (pin "D") (pinfunction "D_D") (pintype "passive"))
      (node (ref "LED2") (pin "1") (pinfunction "-_1") (pintype "passive"))
      (node (ref "LED4") (pin "2") (pinfunction "2_2") (pintype "passive"))
      (node (ref "U1") (pin "1") (pinfunction "PGND_1") (pintype "passive"))
      (node (ref "U1") (pin "11") (pinfunction "EP_11") (pintype "passive"))
      (node (ref "U1") (pin "5") (pinfunction "FB_5") (pintype "passive"))
      (node (ref "U1") (pin "6") (pinfunction "AGND_6") (pintype "passive"))
    )
    (net (code "37") (name "Net-(C3-Pad2)") (class "Default")
      (node (ref "C3") (pin "2") (pinfunction "2_2") (pintype "passive"))
      (node (ref "R3") (pin "2") (pinfunction "2_2") (pintype "passive"))
      (node (ref "T1") (pin "2") (pinfunction "2_2") (pintype "passive"))
    )
    (net (code "38") (name "Net-(C4-Pad1)") (class "Default")
      (node (ref "C4") (pin "1") (pinfunction "1_1") (pintype "passive"))
      (node (ref "R12") (pin "2") (pinfunction "2_2") (pintype "passive"))
      (node (ref "R16") (pin "1") (pinfunction "1_1") (pintype "passive"))
    )
    (net (code "39") (name "Net-(C4-Pad2)") (class "Default")
      (node (ref "C4") (pin "2") (pinfunction "2_2") (pintype "passive"))
      (node (ref "T1") (pin "6") (pinfunction "6_6") (pintype "passive"))
    )
    (net (code "40") (name "Net-(C5-Pad1)") (class "Default")
      (node (ref "C5") (pin "1") (pinfunction "1_1") (pintype "passive"))
      (node (ref "R15") (pin "2") (pinfunction "2_2") (pintype "passive"))
      (node (ref "R17") (pin "1") (pinfunction "1_1") (pintype "passive"))
    )
    (net (code "41") (name "Net-(C5-Pad2)") (class "Default")
      (node (ref "C5") (pin "2") (pinfunction "2_2") (pintype "passive"))
      (node (ref "T1") (pin "8") (pinfunction "8_8") (pintype "passive"))
    )
    (net (code "42") (name "Net-(C6-Pad2)") (class "Default")
      (node (ref "C6") (pin "2") (pinfunction "2_2") (pintype "passive"))
      (node (ref "R10") (pin "1") (pinfunction "1_1") (pintype "passive"))
      (node (ref "R13") (pin "2") (pinfunction "2_2") (pintype "passive"))
      (node (ref "R18") (pin "1") (pinfunction "1_1") (pintype "passive"))
      (node (ref "R19") (pin "2") (pinfunction "2_2") (pintype "passive"))
      (node (ref "R5") (pin "1") (pinfunction "1_1") (pintype "passive"))
      (node (ref "R8") (pin "2") (pinfunction "2_2") (pintype "passive"))
    )
    (net (code "43") (name "Net-(C7-Pad2)") (class "Default")
      (node (ref "C7") (pin "2") (pinfunction "2_2") (pintype "passive"))
      (node (ref "R16") (pin "2") (pinfunction "2_2") (pintype "passive"))
      (node (ref "R17") (pin "2") (pinfunction "2_2") (pintype "passive"))
      (node (ref "T1") (pin "7") (pinfunction "7_7") (pintype "passive"))
    )
    (net (code "44") (name "Net-(C8-Pad2)") (class "Default")
      (node (ref "C8") (pin "2") (pinfunction "2_2") (pintype "passive"))
      (node (ref "R22") (pin "2") (pinfunction "2_2") (pintype "passive"))
      (node (ref "T2") (pin "2") (pinfunction "2_2") (pintype "passive"))
    )
    (net (code "45") (name "Net-(C9-Pad1)") (class "Default")
      (node (ref "C9") (pin "1") (pinfunction "1_1") (pintype "passive"))
      (node (ref "R31") (pin "2") (pinfunction "2_2") (pintype "passive"))
      (node (ref "R35") (pin "1") (pinfunction "1_1") (pintype "passive"))
    )
    (net (code "46") (name "Net-(C9-Pad2)") (class "Default")
      (node (ref "C9") (pin "2") (pinfunction "2_2") (pintype "passive"))
      (node (ref "T2") (pin "6") (pinfunction "6_6") (pintype "passive"))
    )
    (net (code "47") (name "Net-(C10-Pad1)") (class "Default")
      (node (ref "C10") (pin "1") (pinfunction "1_1") (pintype "passive"))
      (node (ref "R34") (pin "2") (pinfunction "2_2") (pintype "passive"))
      (node (ref "R36") (pin "1") (pinfunction "1_1") (pintype "passive"))
    )
    (net (code "48") (name "Net-(C10-Pad2)") (class "Default")
      (node (ref "C10") (pin "2") (pinfunction "2_2") (pintype "passive"))
      (node (ref "T2") (pin "8") (pinfunction "8_8") (pintype "passive"))
    )
    (net (code "49") (name "Net-(C11-Pad2)") (class "Default")
      (node (ref "C11") (pin "2") (pinfunction "2_2") (pintype "passive"))
      (node (ref "R24") (pin "1") (pinfunction "1_1") (pintype "passive"))
      (node (ref "R27") (pin "2") (pinfunction "2_2") (pintype "passive"))
      (node (ref "R29") (pin "1") (pinfunction "1_1") (pintype "passive"))
      (node (ref "R32") (pin "2") (pinfunction "2_2") (pintype "passive"))
      (node (ref "R37") (pin "1") (pinfunction "1_1") (pintype "passive"))
      (node (ref "R38") (pin "2") (pinfunction "2_2") (pintype "passive"))
    )
    (net (code "50") (name "Net-(C12-Pad2)") (class "Default")
      (node (ref "C12") (pin "2") (pinfunction "2_2") (pintype "passive"))
      (node (ref "R35") (pin "2") (pinfunction "2_2") (pintype "passive"))
      (node (ref "R36") (pin "2") (pinfunction "2_2") (pintype "passive"))
      (node (ref "T2") (pin "7") (pinfunction "7_7") (pintype "passive"))
    )
    (net (code "51") (name "Net-(J5-Pad4)") (class "Default")
      (node (ref "J5") (pin "4") (pinfunction "4_4") (pintype "passive"))
      (node (ref "R7") (pin "1") (pinfunction "1_1") (pintype "passive"))
    )
    (net (code "52") (name "Net-(J5-Pad5)") (class "Default")
      (node (ref "J5") (pin "5") (pinfunction "5_5") (pintype "passive"))
      (node (ref "R9") (pin "1") (pinfunction "1_1") (pintype "passive"))
    )
    (net (code "53") (name "Net-(J5-Pad7)") (class "Default")
      (node (ref "J5") (pin "7") (pinfunction "7_7") (pintype "passive"))
      (node (ref "R11") (pin "1") (pinfunction "1_1") (pintype "passive"))
    )
    (net (code "54") (name "Net-(J5-Pad8)") (class "Default")
      (node (ref "J5") (pin "8") (pinfunction "8_8") (pintype "passive"))
      (node (ref "R14") (pin "1") (pinfunction "1_1") (pintype "passive"))
    )
    (net (code "55") (name "Net-(J6-Pad4)") (class "Default")
      (node (ref "J6") (pin "4") (pinfunction "4_4") (pintype "passive"))
      (node (ref "R26") (pin "1") (pinfunction "1_1") (pintype "passive"))
    )
    (net (code "56") (name "Net-(J6-Pad5)") (class "Default")
      (node (ref "J6") (pin "5") (pinfunction "5_5") (pintype "passive"))
      (node (ref "R28") (pin "1") (pinfunction "1_1") (pintype "passive"))
    )
    (net (code "57") (name "Net-(J6-Pad7)") (class "Default")
      (node (ref "J6") (pin "7") (pinfunction "7_7") (pintype "passive"))
      (node (ref "R30") (pin "1") (pinfunction "1_1") (pintype "passive"))
    )
    (net (code "58") (name "Net-(J6-Pad8)") (class "Default")
      (node (ref "J6") (pin "8") (pinfunction "8_8") (pintype "passive"))
      (node (ref "R33") (pin "1") (pinfunction "1_1") (pintype "passive"))
    )
    (net (code "59") (name "Net-(R1-Pad2)") (class "Default")
      (node (ref "R1") (pin "2") (pinfunction "2_2") (pintype "passive"))
      (node (ref "R4") (pin "2") (pinfunction "2_2") (pintype "passive"))
      (node (ref "T1") (pin "1") (pinfunction "1_1") (pintype "passive"))
    )
    (net (code "60") (name "Net-(R2-Pad2)") (class "Default")
      (node (ref "R2") (pin "2") (pinfunction "2_2") (pintype "passive"))
      (node (ref "R6") (pin "2") (pinfunction "2_2") (pintype "passive"))
      (node (ref "T1") (pin "3") (pinfunction "3_3") (pintype "passive"))
    )
    (net (code "61") (name "Net-(R5-Pad2)") (class "Default")
      (node (ref "R5") (pin "2") (pinfunction "2_2") (pintype "passive"))
      (node (ref "T1") (pin "15") (pinfunction "15_15") (pintype "passive"))
    )
    (net (code "62") (name "Net-(R7-Pad2)") (class "Default")
      (node (ref "R7") (pin "2") (pinfunction "2_2") (pintype "passive"))
      (node (ref "R8") (pin "1") (pinfunction "1_1") (pintype "passive"))
      (node (ref "R9") (pin "2") (pinfunction "2_2") (pintype "passive"))
    )
    (net (code "63") (name "Net-(R10-Pad2)") (class "Default")
      (node (ref "R10") (pin "2") (pinfunction "2_2") (pintype "passive"))
      (node (ref "T1") (pin "10") (pinfunction "10_10") (pintype "passive"))
    )
    (net (code "64") (name "Net-(R11-Pad2)") (class "Default")
      (node (ref "R11") (pin "2") (pinfunction "2_2") (pintype "passive"))
      (node (ref "R13") (pin "1") (pinfunction "1_1") (pintype "passive"))
      (node (ref "R14") (pin "2") (pinfunction "2_2") (pintype "passive"))
    )
    (net (code "65") (name "Net-(R20-Pad2)") (class "Default")
      (node (ref "R20") (pin "2") (pinfunction "2_2") (pintype "passive"))
      (node (ref "R23") (pin "2") (pinfunction "2_2") (pintype "passive"))
      (node (ref "T2") (pin "1") (pinfunction "1_1") (pintype "passive"))
    )
    (net (code "66") (name "Net-(R21-Pad2)") (class "Default")
      (node (ref "R21") (pin "2") (pinfunction "2_2") (pintype "passive"))
      (node (ref "R25") (pin "2") (pinfunction "2_2") (pintype "passive"))
      (node (ref "T2") (pin "3") (pinfunction "3_3") (pintype "passive"))
    )
    (net (code "67") (name "Net-(R24-Pad2)") (class "Default")
      (node (ref "R24") (pin "2") (pinfunction "2_2") (pintype "passive"))
      (node (ref "T2") (pin "15") (pinfunction "15_15") (pintype "passive"))
    )
    (net (code "68") (name "Net-(R26-Pad2)") (class "Default")
      (node (ref "R26") (pin "2") (pinfunction "2_2") (pintype "passive"))
      (node (ref "R27") (pin "1") (pinfunction "1_1") (pintype "passive"))
      (node (ref "R28") (pin "2") (pinfunction "2_2") (pintype "passive"))
    )
    (net (code "69") (name "Net-(R29-Pad2)") (class "Default")
      (node (ref "R29") (pin "2") (pinfunction "2_2") (pintype "passive"))
      (node (ref "T2") (pin "10") (pinfunction "10_10") (pintype "passive"))
    )
    (net (code "70") (name "Net-(R30-Pad2)") (class "Default")
      (node (ref "R30") (pin "2") (pinfunction "2_2") (pintype "passive"))
      (node (ref "R32") (pin "1") (pinfunction "1_1") (pintype "passive"))
      (node (ref "R33") (pin "2") (pinfunction "2_2") (pintype "passive"))
    )
    (net (code "71") (name "Net-(U1-SW)") (class "Default")
      (node (ref "L1") (pin "1") (pinfunction "1_1") (pintype "passive"))
      (node (ref "U1") (pin "9") (pinfunction "SW_9") (pintype "passive"))
    )
    (net (code "72") (name "unconnected-(J4-Pad06)") (class "Default")
      (node (ref "J4") (pin "06") (pinfunction "06_06") (pintype "passive+no_connect"))
    )
    (net (code "73") (name "unconnected-(U1-NC-Pad4)") (class "Default")
      (node (ref "U1") (pin "4") (pinfunction "NC_4") (pintype "passive+no_connect"))
    )
    (net (code "74") (name "unconnected-(U1-PG-Pad7)") (class "Default")
      (node (ref "U1") (pin "7") (pinfunction "PG_7") (pintype "passive+no_connect"))
    )
  )
)
